# V2-1layer.net
KiCad netlist of a schematic drawn in EAGLE
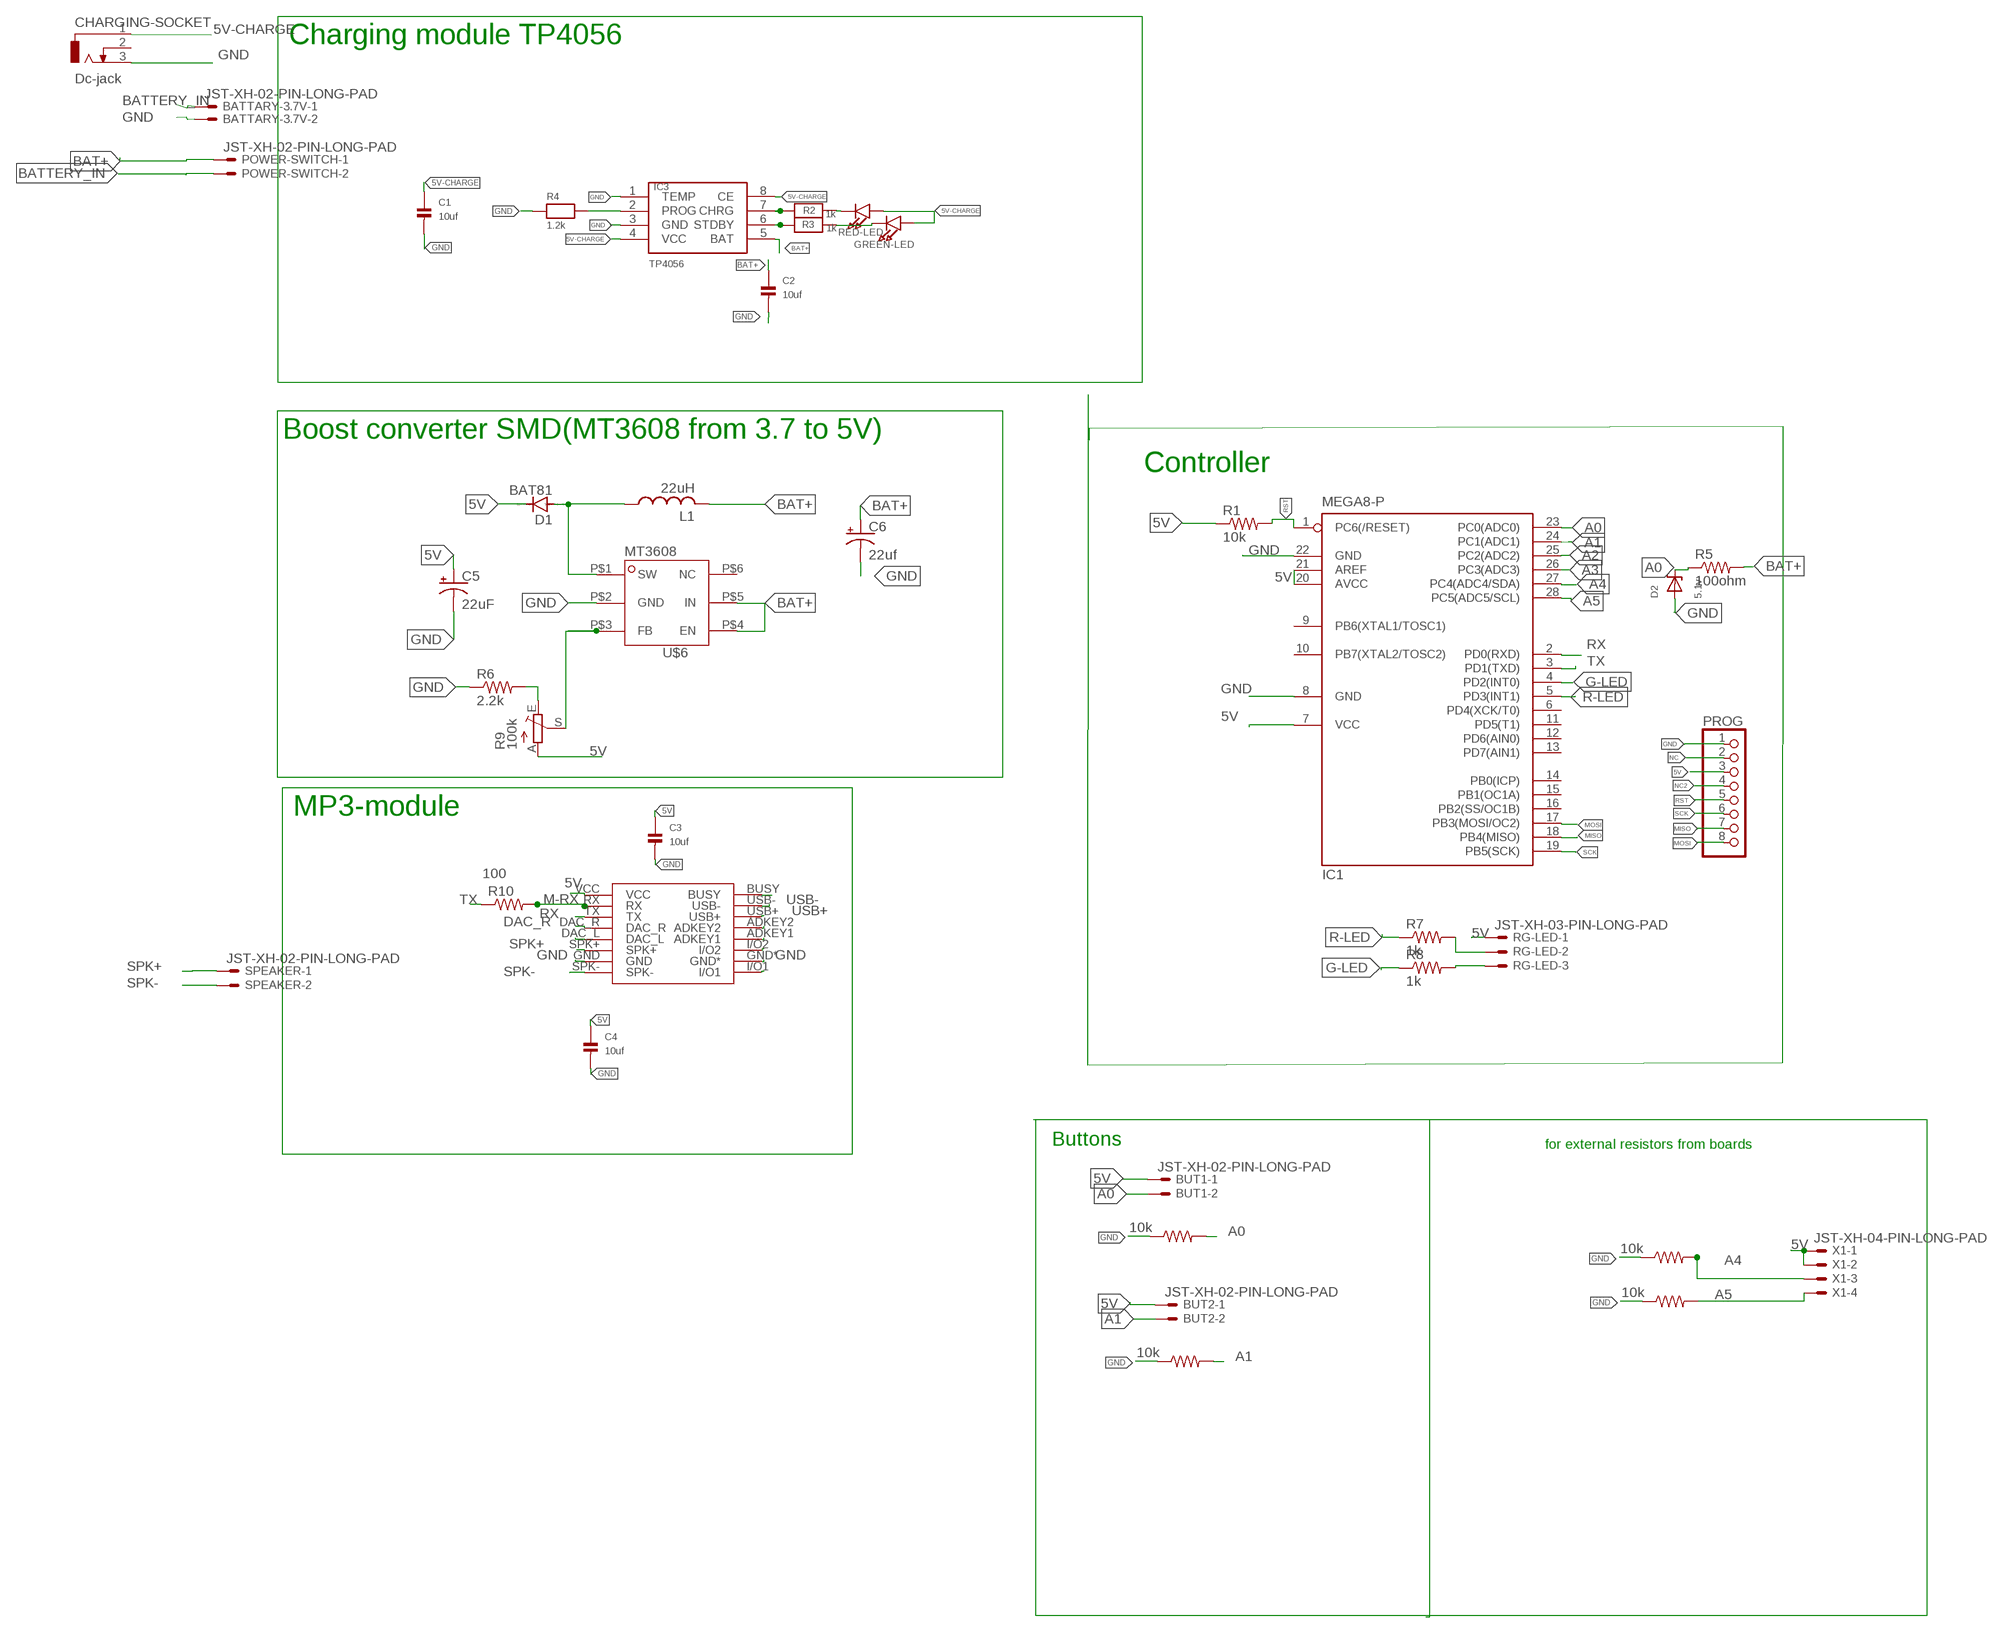
[diagram p0: schematic, sheet 1]

(export (version "E")
  (design (tool "Eeschema 10.0.6"))
  (components
    (comp (ref "BATTARY-3.7V")
      (value "JST-XH-02-PIN-LONG-PAD")
      (footprint "eagle-import:JST-XH-02-PACKAGE-LONG-PAD")
      (libsource (lib "eagle-import") (part "JST-XH-02-PIN-LONG-PAD"))
    )
    (comp (ref "BUT1")
      (value "JST-XH-02-PIN-LONG-PAD")
      (footprint "eagle-import:JST-XH-02-PACKAGE-LONG-PAD")
      (libsource (lib "eagle-import") (part "JST-XH-02-PIN-LONG-PAD"))
    )
    (comp (ref "BUT2")
      (value "JST-XH-02-PIN-LONG-PAD")
      (footprint "eagle-import:JST-XH-02-PACKAGE-LONG-PAD")
      (libsource (lib "eagle-import") (part "JST-XH-02-PIN-LONG-PAD"))
    )
    (comp (ref "C1")
      (value "10uf")
      (footprint "eagle-import:0805")
      (libsource (lib "eagle-import") (part "CAP_CERAMIC0805"))
    )
    (comp (ref "C2")
      (value "10uf")
      (footprint "eagle-import:0805")
      (libsource (lib "eagle-import") (part "CAP_CERAMIC0805"))
    )
    (comp (ref "C3")
      (value "10uf")
      (footprint "eagle-import:0805")
      (libsource (lib "eagle-import") (part "CAP_CERAMIC0805"))
    )
    (comp (ref "C4")
      (value "10uf")
      (footprint "eagle-import:0805")
      (libsource (lib "eagle-import") (part "CAP_CERAMIC0805"))
    )
    (comp (ref "C5")
      (value "22uF")
      (footprint "eagle-import:E2,5-6E")
      (libsource (lib "eagle-import") (part "CPOL-USE2,5-6E"))
    )
    (comp (ref "C6")
      (value "22uf")
      (footprint "eagle-import:E2,5-6E")
      (libsource (lib "eagle-import") (part "CPOL-USE2,5-6E"))
    )
    (comp (ref "CHARGING-SOCKET")
      (value "Dc-jack")
      (footprint "eagle-import:DCJ0303")
      (libsource (lib "eagle-import") (part "CON_JACK"))
    )
    (comp (ref "D1")
      (value "BAT81")
      (footprint "eagle-import:DO34-7")
      (libsource (lib "eagle-import") (part "BAT81"))
    )
    (comp (ref "D2")
      (value "5.1v")
      (footprint "eagle-import:SMADIODE")
      (libsource (lib "eagle-import") (part "DIODE-ZENER"))
    )
    (comp (ref "GREEN-LED")
      (value "LED0805")
      (footprint "eagle-import:CHIPLED_0805")
      (libsource (lib "eagle-import") (part "LED0805"))
    )
    (comp (ref "IC1")
      (value "MEGA8-P")
      (footprint "eagle-import:DIL28-3")
      (libsource (lib "eagle-import") (part "MEGA8-P"))
    )
    (comp (ref "IC3")
      (value "TP4056")
      (footprint "eagle-import:SOP-8")
      (libsource (lib "eagle-import") (part "TP4056"))
    )
    (comp (ref "KEYPADS")
      (value "10k")
      (footprint "eagle-import:0204_7")
      (libsource (lib "eagle-import") (part "RES-7"))
    )
    (comp (ref "KEYPADS1")
      (value "10k")
      (footprint "eagle-import:0204_7")
      (libsource (lib "eagle-import") (part "RES-7"))
    )
    (comp (ref "KEYPADS2")
      (value "10k")
      (footprint "eagle-import:0204_7")
      (libsource (lib "eagle-import") (part "RES-7"))
    )
    (comp (ref "KEYPADS3")
      (value "10k")
      (footprint "eagle-import:0204_7")
      (libsource (lib "eagle-import") (part "RES-7"))
    )
    (comp (ref "L1")
      (value "22uH")
      (footprint "eagle-import:L1812")
      (libsource (lib "eagle-import") (part "L-USL1812"))
    )
    (comp (ref "POWER-SWITCH")
      (value "JST-XH-02-PIN-LONG-PAD")
      (footprint "eagle-import:JST-XH-02-PACKAGE-LONG-PAD")
      (libsource (lib "eagle-import") (part "JST-XH-02-PIN-LONG-PAD"))
    )
    (comp (ref "PROG")
      (value "PINHD-1X8")
      (footprint "eagle-import:1X08")
      (libsource (lib "eagle-import") (part "PINHD-1X8"))
    )
    (comp (ref "R1")
      (value "10k")
      (footprint "eagle-import:0204_7")
      (libsource (lib "eagle-import") (part "R-US_0204/7"))
    )
    (comp (ref "R2")
      (value "1k")
      (footprint "eagle-import:_0805")
      (libsource (lib "eagle-import") (part "RESISTOR_0805"))
    )
    (comp (ref "R3")
      (value "1k")
      (footprint "eagle-import:_0805")
      (libsource (lib "eagle-import") (part "RESISTOR_0805"))
    )
    (comp (ref "R4")
      (value "1.2k")
      (footprint "eagle-import:_0805")
      (libsource (lib "eagle-import") (part "RESISTOR_0805"))
    )
    (comp (ref "R5")
      (value "100ohm")
      (footprint "eagle-import:0204_7")
      (libsource (lib "eagle-import") (part "R-US_0204/7"))
    )
    (comp (ref "R6")
      (value "2.2k")
      (footprint "eagle-import:M0805")
      (libsource (lib "eagle-import") (part "R-US_M0805"))
    )
    (comp (ref "R7")
      (value "1k")
      (footprint "eagle-import:0204_7")
      (libsource (lib "eagle-import") (part "R-US_0204/7"))
    )
    (comp (ref "R8")
      (value "1k")
      (footprint "eagle-import:0204_7")
      (libsource (lib "eagle-import") (part "R-US_0204/7"))
    )
    (comp (ref "R9")
      (value "100k")
      (footprint "eagle-import:B25U")
      (libsource (lib "eagle-import") (part "TRIM_EU-B25U"))
    )
    (comp (ref "R10")
      (value "100")
      (footprint "eagle-import:0204_7")
      (libsource (lib "eagle-import") (part "RES-7"))
    )
    (comp (ref "RED-LED")
      (value "LED0805")
      (footprint "eagle-import:CHIPLED_0805")
      (libsource (lib "eagle-import") (part "LED0805"))
    )
    (comp (ref "RG-LED")
      (value "JST-XH-03-PIN-LONG-PAD")
      (footprint "eagle-import:JST-XH-03-PACKAGE-LONG-PAD")
      (libsource (lib "eagle-import") (part "JST-XH-03-PIN-LONG-PAD"))
    )
    (comp (ref "SPEAKER")
      (value "JST-XH-02-PIN-LONG-PAD")
      (footprint "eagle-import:JST-XH-02-PACKAGE-LONG-PAD")
      (libsource (lib "eagle-import") (part "JST-XH-02-PIN-LONG-PAD"))
    )
    (comp (ref "U$2")
      (value "MP3_MODULE")
      (footprint "eagle-import:MP3_MODULE")
      (libsource (lib "eagle-import") (part "MP3_MODULE"))
    )
    (comp (ref "U$6")
      (value "MT3608SOT23-6")
      (footprint "eagle-import:SOT23-6")
      (libsource (lib "eagle-import") (part "MT3608SOT23-6"))
    )
    (comp (ref "X1")
      (value "JST-XH-04-PIN-LONG-PAD")
      (footprint "eagle-import:JST-XH-04-PACKAGE-LONG-PAD")
      (libsource (lib "eagle-import") (part "JST-XH-04-PIN-LONG-PAD"))
    )
  )
  (nets
    (net (code "1") (name "/DAC_R") (class "Default")
      (node (ref "U$2") (pin "DAC_R") (pinfunction "DAC_R_DAC_R") (pintype "bidirectional"))
    )
    (net (code "2") (name "/M-RX") (class "Default")
      (node (ref "R10") (pin "2") (pinfunction "2_2") (pintype "passive"))
      (node (ref "U$2") (pin "RX") (pinfunction "RX_RX") (pintype "bidirectional"))
    )
    (net (code "3") (name "/RX") (class "Default")
      (node (ref "IC1") (pin "2") (pinfunction "PD0(RXD)_2") (pintype "bidirectional"))
      (node (ref "U$2") (pin "TX") (pinfunction "TX_TX") (pintype "bidirectional"))
    )
    (net (code "4") (name "/SPK+") (class "Default")
      (node (ref "SPEAKER") (pin "1") (pinfunction "S_1") (pintype "passive"))
      (node (ref "U$2") (pin "SPK+") (pinfunction "SPK+_SPK+") (pintype "bidirectional"))
    )
    (net (code "5") (name "/SPK-") (class "Default")
      (node (ref "SPEAKER") (pin "2") (pinfunction "S_2") (pintype "passive"))
      (node (ref "U$2") (pin "SPK-") (pinfunction "SPK-_SPK-") (pintype "bidirectional"))
    )
    (net (code "6") (name "/TX") (class "Default")
      (node (ref "IC1") (pin "3") (pinfunction "PD1(TXD)_3") (pintype "bidirectional"))
      (node (ref "R10") (pin "1") (pinfunction "1_1") (pintype "passive"))
    )
    (net (code "7") (name "/USB+") (class "Default")
      (node (ref "U$2") (pin "USB+") (pinfunction "USB+_USB+") (pintype "bidirectional"))
    )
    (net (code "8") (name "/USB-") (class "Default")
      (node (ref "U$2") (pin "USB-") (pinfunction "USB-_USB-") (pintype "bidirectional"))
    )
    (net (code "9") (name "5V") (class "Default")
      (node (ref "BUT1") (pin "1") (pinfunction "S_1") (pintype "passive"))
      (node (ref "BUT2") (pin "1") (pinfunction "S_1") (pintype "passive"))
      (node (ref "C3") (pin "1") (pinfunction "P$1_1") (pintype "passive"))
      (node (ref "C4") (pin "1") (pinfunction "P$1_1") (pintype "passive"))
      (node (ref "C5") (pin "+") (pinfunction "+_+") (pintype "passive"))
      (node (ref "D1") (pin "C") (pinfunction "C_C") (pintype "passive"))
      (node (ref "IC1") (pin "20") (pinfunction "AVCC_20") (pintype "power_in"))
      (node (ref "IC1") (pin "21") (pinfunction "AREF_21") (pintype "passive"))
      (node (ref "IC1") (pin "7") (pinfunction "VCC_7") (pintype "power_in"))
      (node (ref "PROG") (pin "3") (pinfunction "3_3") (pintype "passive"))
      (node (ref "R1") (pin "1") (pinfunction "1_1") (pintype "passive"))
      (node (ref "R9") (pin "A") (pinfunction "A_A") (pintype "passive"))
      (node (ref "RG-LED") (pin "1") (pinfunction "S_1") (pintype "passive"))
      (node (ref "U$2") (pin "VCC") (pinfunction "VCC_VCC") (pintype "bidirectional"))
      (node (ref "X1") (pin "1") (pinfunction "S_1") (pintype "passive"))
      (node (ref "X1") (pin "2") (pinfunction "S_2") (pintype "passive"))
    )
    (net (code "10") (name "5V-CHARGE") (class "Default")
      (node (ref "C1") (pin "1") (pinfunction "P$1_1") (pintype "passive"))
      (node (ref "CHARGING-SOCKET") (pin "1") (pinfunction "1_1") (pintype "passive"))
      (node (ref "GREEN-LED") (pin "A") (pinfunction "A_A") (pintype "passive"))
      (node (ref "IC3") (pin "4") (pinfunction "VCC_4") (pintype "bidirectional"))
      (node (ref "IC3") (pin "8") (pinfunction "CE_8") (pintype "bidirectional"))
      (node (ref "RED-LED") (pin "A") (pinfunction "A_A") (pintype "passive"))
    )
    (net (code "11") (name "A0") (class "Default")
      (node (ref "BUT1") (pin "2") (pinfunction "S_2") (pintype "passive"))
      (node (ref "D2") (pin "C") (pinfunction "C_C") (pintype "passive"))
      (node (ref "IC1") (pin "23") (pinfunction "PC0(ADC0)_23") (pintype "bidirectional"))
      (node (ref "KEYPADS") (pin "2") (pinfunction "2_2") (pintype "passive"))
      (node (ref "R5") (pin "1") (pinfunction "1_1") (pintype "passive"))
    )
    (net (code "12") (name "A1") (class "Default")
      (node (ref "BUT2") (pin "2") (pinfunction "S_2") (pintype "passive"))
      (node (ref "IC1") (pin "24") (pinfunction "PC1(ADC1)_24") (pintype "bidirectional"))
      (node (ref "KEYPADS3") (pin "2") (pinfunction "2_2") (pintype "passive"))
    )
    (net (code "13") (name "A2") (class "Default")
      (node (ref "IC1") (pin "25") (pinfunction "PC2(ADC2)_25") (pintype "bidirectional"))
    )
    (net (code "14") (name "A3") (class "Default")
      (node (ref "IC1") (pin "26") (pinfunction "PC3(ADC3)_26") (pintype "bidirectional"))
    )
    (net (code "15") (name "A4") (class "Default")
      (node (ref "IC1") (pin "27") (pinfunction "PC4(ADC4/SDA)_27") (pintype "bidirectional"))
      (node (ref "KEYPADS1") (pin "2") (pinfunction "2_2") (pintype "passive"))
      (node (ref "X1") (pin "3") (pinfunction "S_3") (pintype "passive"))
    )
    (net (code "16") (name "A5") (class "Default")
      (node (ref "IC1") (pin "28") (pinfunction "PC5(ADC5/SCL)_28") (pintype "bidirectional"))
      (node (ref "KEYPADS2") (pin "2") (pinfunction "2_2") (pintype "passive"))
      (node (ref "X1") (pin "4") (pinfunction "S_4") (pintype "passive"))
    )
    (net (code "17") (name "BAT+") (class "Default")
      (node (ref "C2") (pin "1") (pinfunction "P$1_1") (pintype "passive"))
      (node (ref "C6") (pin "+") (pinfunction "+_+") (pintype "passive"))
      (node (ref "IC3") (pin "5") (pinfunction "BAT_5") (pintype "bidirectional"))
      (node (ref "L1") (pin "2") (pinfunction "2_2") (pintype "passive"))
      (node (ref "POWER-SWITCH") (pin "1") (pinfunction "S_1") (pintype "passive"))
      (node (ref "R5") (pin "2") (pinfunction "2_2") (pintype "passive"))
      (node (ref "U$6") (pin "P$4") (pinfunction "EN_P$4") (pintype "bidirectional"))
      (node (ref "U$6") (pin "P$5") (pinfunction "IN_P$5") (pintype "bidirectional"))
    )
    (net (code "18") (name "BATTERY_IN") (class "Default")
      (node (ref "BATTARY-3.7V") (pin "1") (pinfunction "S_1") (pintype "passive"))
      (node (ref "POWER-SWITCH") (pin "2") (pinfunction "S_2") (pintype "passive"))
    )
    (net (code "19") (name "G-LED") (class "Default")
      (node (ref "IC1") (pin "4") (pinfunction "PD2(INT0)_4") (pintype "bidirectional"))
      (node (ref "R8") (pin "1") (pinfunction "1_1") (pintype "passive"))
    )
    (net (code "20") (name "GND") (class "Default")
      (node (ref "BATTARY-3.7V") (pin "2") (pinfunction "S_2") (pintype "passive"))
      (node (ref "C1") (pin "2") (pinfunction "P$2_2") (pintype "passive"))
      (node (ref "C2") (pin "2") (pinfunction "P$2_2") (pintype "passive"))
      (node (ref "C3") (pin "2") (pinfunction "P$2_2") (pintype "passive"))
      (node (ref "C4") (pin "2") (pinfunction "P$2_2") (pintype "passive"))
      (node (ref "C5") (pin "-") (pinfunction "-_-") (pintype "passive"))
      (node (ref "C6") (pin "-") (pinfunction "-_-") (pintype "passive"))
      (node (ref "CHARGING-SOCKET") (pin "3") (pinfunction "3_3") (pintype "passive"))
      (node (ref "D2") (pin "A") (pinfunction "A_A") (pintype "passive"))
      (node (ref "IC1") (pin "22") (pinfunction "GND_22") (pintype "power_in"))
      (node (ref "IC1") (pin "8") (pinfunction "GND_8") (pintype "power_in"))
      (node (ref "IC3") (pin "1") (pinfunction "TEMP_1") (pintype "bidirectional"))
      (node (ref "IC3") (pin "3") (pinfunction "GND_3") (pintype "bidirectional"))
      (node (ref "KEYPADS") (pin "1") (pinfunction "1_1") (pintype "passive"))
      (node (ref "KEYPADS1") (pin "1") (pinfunction "1_1") (pintype "passive"))
      (node (ref "KEYPADS2") (pin "1") (pinfunction "1_1") (pintype "passive"))
      (node (ref "KEYPADS3") (pin "1") (pinfunction "1_1") (pintype "passive"))
      (node (ref "PROG") (pin "1") (pinfunction "1_1") (pintype "passive"))
      (node (ref "R4") (pin "1") (pinfunction "1_1") (pintype "passive"))
      (node (ref "R6") (pin "1") (pinfunction "1_1") (pintype "passive"))
      (node (ref "U$2") (pin "GND") (pinfunction "GND_GND") (pintype "bidirectional"))
      (node (ref "U$2") (pin "GND*") (pinfunction "GND*_GND*") (pintype "bidirectional"))
      (node (ref "U$6") (pin "P$2") (pinfunction "GND_P$2") (pintype "bidirectional"))
    )
    (net (code "21") (name "MISO") (class "Default")
      (node (ref "IC1") (pin "18") (pinfunction "PB4(MISO)_18") (pintype "bidirectional"))
      (node (ref "PROG") (pin "7") (pinfunction "7_7") (pintype "passive"))
    )
    (net (code "22") (name "MOSI") (class "Default")
      (node (ref "IC1") (pin "17") (pinfunction "PB3(MOSI/OC2)_17") (pintype "bidirectional"))
      (node (ref "PROG") (pin "8") (pinfunction "8_8") (pintype "passive"))
    )
    (net (code "23") (name "NC") (class "Default")
      (node (ref "PROG") (pin "2") (pinfunction "2_2") (pintype "passive"))
    )
    (net (code "24") (name "NC2") (class "Default")
      (node (ref "PROG") (pin "4") (pinfunction "4_4") (pintype "passive"))
    )
    (net (code "25") (name "Net-(GREEN-LED-PadC)") (class "Default")
      (node (ref "GREEN-LED") (pin "C") (pinfunction "C_C") (pintype "passive"))
      (node (ref "R3") (pin "2") (pinfunction "2_2") (pintype "passive"))
    )
    (net (code "26") (name "Net-(IC3-CHRG)") (class "Default")
      (node (ref "IC3") (pin "7") (pinfunction "CHRG_7") (pintype "bidirectional"))
      (node (ref "R2") (pin "1") (pinfunction "1_1") (pintype "passive"))
    )
    (net (code "27") (name "Net-(IC3-PROG)") (class "Default")
      (node (ref "IC3") (pin "2") (pinfunction "PROG_2") (pintype "bidirectional"))
      (node (ref "R4") (pin "2") (pinfunction "2_2") (pintype "passive"))
    )
    (net (code "28") (name "Net-(IC3-STDBY)") (class "Default")
      (node (ref "IC3") (pin "6") (pinfunction "STDBY_6") (pintype "bidirectional"))
      (node (ref "R3") (pin "1") (pinfunction "1_1") (pintype "passive"))
    )
    (net (code "29") (name "Net-(R2-Pad2)") (class "Default")
      (node (ref "R2") (pin "2") (pinfunction "2_2") (pintype "passive"))
      (node (ref "RED-LED") (pin "C") (pinfunction "C_C") (pintype "passive"))
    )
    (net (code "30") (name "Net-(R6-Pad2)") (class "Default")
      (node (ref "R6") (pin "2") (pinfunction "2_2") (pintype "passive"))
      (node (ref "R9") (pin "E") (pinfunction "E_E") (pintype "passive"))
    )
    (net (code "31") (name "Net-(RG-LEDB-S)") (class "Default")
      (node (ref "R7") (pin "2") (pinfunction "2_2") (pintype "passive"))
      (node (ref "RG-LED") (pin "2") (pinfunction "S_2") (pintype "passive"))
    )
    (net (code "32") (name "Net-(RG-LEDC-S)") (class "Default")
      (node (ref "R8") (pin "2") (pinfunction "2_2") (pintype "passive"))
      (node (ref "RG-LED") (pin "3") (pinfunction "S_3") (pintype "passive"))
    )
    (net (code "33") (name "Net-(U$6-FB)") (class "Default")
      (node (ref "R9") (pin "S") (pinfunction "S_S") (pintype "passive"))
      (node (ref "U$6") (pin "P$3") (pinfunction "FB_P$3") (pintype "bidirectional"))
    )
    (net (code "34") (name "Net-(U$6-SW)") (class "Default")
      (node (ref "D1") (pin "A") (pinfunction "A_A") (pintype "passive"))
      (node (ref "L1") (pin "1") (pinfunction "1_1") (pintype "passive"))
      (node (ref "U$6") (pin "P$1") (pinfunction "SW_P$1") (pintype "bidirectional"))
    )
    (net (code "35") (name "R-LED") (class "Default")
      (node (ref "IC1") (pin "5") (pinfunction "PD3(INT1)_5") (pintype "bidirectional"))
      (node (ref "R7") (pin "1") (pinfunction "1_1") (pintype "passive"))
    )
    (net (code "36") (name "RST") (class "Default")
      (node (ref "IC1") (pin "1") (pinfunction "PC6(/RESET)_1") (pintype "bidirectional"))
      (node (ref "PROG") (pin "5") (pinfunction "5_5") (pintype "passive"))
      (node (ref "R1") (pin "2") (pinfunction "2_2") (pintype "passive"))
    )
    (net (code "37") (name "SCK") (class "Default")
      (node (ref "IC1") (pin "19") (pinfunction "PB5(SCK)_19") (pintype "bidirectional"))
      (node (ref "PROG") (pin "6") (pinfunction "6_6") (pintype "passive"))
    )
    (net (code "38") (name "unconnected-(CHARGING-SOCKET-Pad2)") (class "Default")
      (node (ref "CHARGING-SOCKET") (pin "2") (pinfunction "2_2") (pintype "passive"))
    )
    (net (code "39") (name "unconnected-(IC1-PB0(ICP)-Pad14)") (class "Default")
      (node (ref "IC1") (pin "14") (pinfunction "PB0(ICP)_14") (pintype "bidirectional"))
    )
    (net (code "40") (name "unconnected-(IC1-PB1(OC1A)-Pad15)") (class "Default")
      (node (ref "IC1") (pin "15") (pinfunction "PB1(OC1A)_15") (pintype "bidirectional"))
    )
    (net (code "41") (name "unconnected-(IC1-PB2(SS{slash}OC1B)-Pad16)") (class "Default")
      (node (ref "IC1") (pin "16") (pinfunction "PB2(SS/OC1B)_16") (pintype "bidirectional"))
    )
    (net (code "42") (name "unconnected-(IC1-PB6(XTAL1{slash}TOSC1)-Pad9)") (class "Default")
      (node (ref "IC1") (pin "9") (pinfunction "PB6(XTAL1/TOSC1)_9") (pintype "bidirectional"))
    )
    (net (code "43") (name "unconnected-(IC1-PB7(XTAL2{slash}TOSC2)-Pad10)") (class "Default")
      (node (ref "IC1") (pin "10") (pinfunction "PB7(XTAL2/TOSC2)_10") (pintype "bidirectional"))
    )
    (net (code "44") (name "unconnected-(IC1-PD4(XCK{slash}T0)-Pad6)") (class "Default")
      (node (ref "IC1") (pin "6") (pinfunction "PD4(XCK/T0)_6") (pintype "bidirectional"))
    )
    (net (code "45") (name "unconnected-(IC1-PD5(T1)-Pad11)") (class "Default")
      (node (ref "IC1") (pin "11") (pinfunction "PD5(T1)_11") (pintype "bidirectional"))
    )
    (net (code "46") (name "unconnected-(IC1-PD6(AIN0)-Pad12)") (class "Default")
      (node (ref "IC1") (pin "12") (pinfunction "PD6(AIN0)_12") (pintype "bidirectional"))
    )
    (net (code "47") (name "unconnected-(IC1-PD7(AIN1)-Pad13)") (class "Default")
      (node (ref "IC1") (pin "13") (pinfunction "PD7(AIN1)_13") (pintype "bidirectional"))
    )
    (net (code "48") (name "unconnected-(U$2-PadADKEY1)") (class "Default")
      (node (ref "U$2") (pin "ADKEY1") (pinfunction "ADKEY1_ADKEY1") (pintype "bidirectional"))
    )
    (net (code "49") (name "unconnected-(U$2-PadADKEY2)") (class "Default")
      (node (ref "U$2") (pin "ADKEY2") (pinfunction "ADKEY2_ADKEY2") (pintype "bidirectional"))
    )
    (net (code "50") (name "unconnected-(U$2-PadBUSY)") (class "Default")
      (node (ref "U$2") (pin "BUSY") (pinfunction "BUSY_BUSY") (pintype "bidirectional"))
    )
    (net (code "51") (name "unconnected-(U$2-PadDAC_L)") (class "Default")
      (node (ref "U$2") (pin "DAC_L") (pinfunction "DAC_L_DAC_L") (pintype "bidirectional"))
    )
    (net (code "52") (name "unconnected-(U$2-PadI{slash}O1)") (class "Default")
      (node (ref "U$2") (pin "I/O1") (pinfunction "I/O1_I/O1") (pintype "bidirectional"))
    )
    (net (code "53") (name "unconnected-(U$2-PadI{slash}O2)") (class "Default")
      (node (ref "U$2") (pin "I/O2") (pinfunction "I/O2_I/O2") (pintype "bidirectional"))
    )
    (net (code "54") (name "unconnected-(U$6-NC-PadP$6)") (class "Default")
      (node (ref "U$6") (pin "P$6") (pinfunction "NC_P$6") (pintype "bidirectional"))
    )
  )
)
